# realsense_bridge.net
KiCad netlist of a schematic drawn in Altium Designer
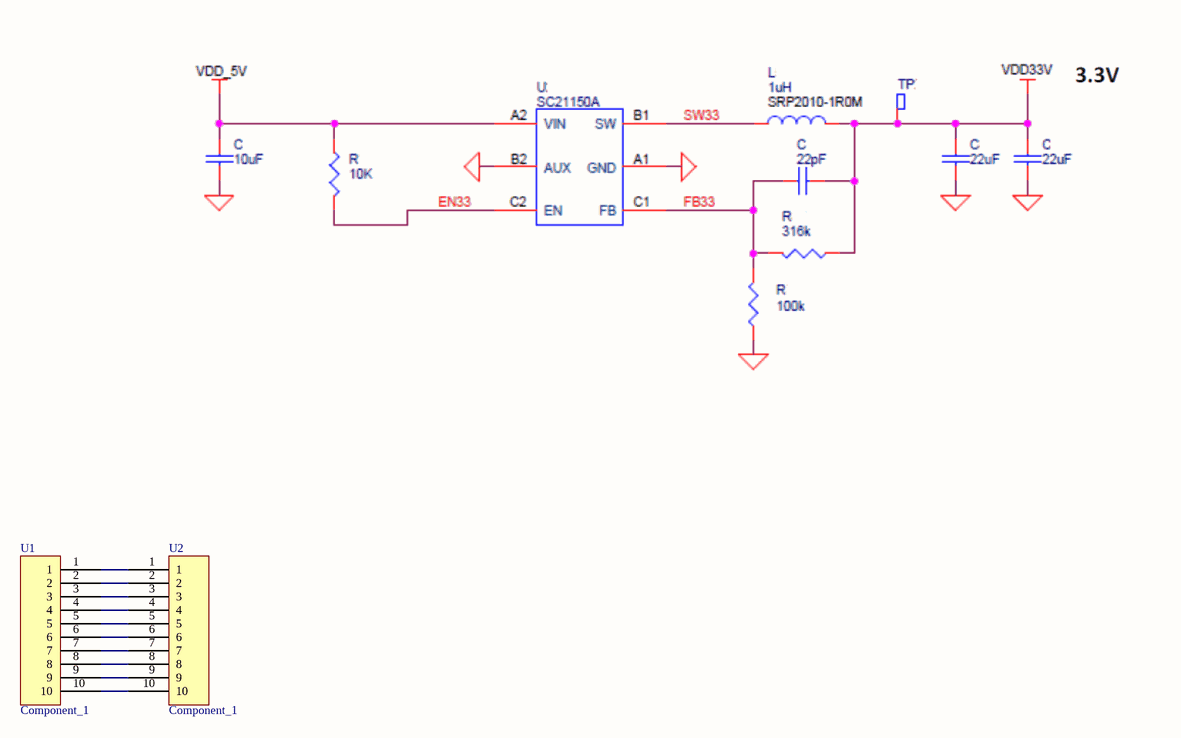
[diagram p0: realsense_bridge.SchDoc]

(export (version "E")
  (design (tool "Eeschema 10.0.6"))
  (components
    (comp (ref "U1")
      (value "Component_1")
      (footprint "IPEX-20346-10T")
      (libsource (lib "") (part "Component_1_1"))
    )
    (comp (ref "U2")
      (value "Component_1")
      (footprint "FPC0.5 2H-WS-10P")
      (libsource (lib "Schlib1") (part "Component_1"))
    )
  )
  (nets
    (net (code "1") (name "Net-(U1-Pad1)") (class "Default")
      (node (ref "U1") (pin "1") (pinfunction "1_1") (pintype "passive"))
      (node (ref "U2") (pin "1") (pinfunction "1_1") (pintype "passive"))
    )
    (net (code "2") (name "Net-(U1-Pad2)") (class "Default")
      (node (ref "U1") (pin "2") (pinfunction "2_2") (pintype "passive"))
      (node (ref "U2") (pin "2") (pinfunction "2_2") (pintype "passive"))
    )
    (net (code "3") (name "Net-(U1-Pad3)") (class "Default")
      (node (ref "U1") (pin "3") (pinfunction "3_3") (pintype "passive"))
      (node (ref "U2") (pin "3") (pinfunction "3_3") (pintype "passive"))
    )
    (net (code "4") (name "Net-(U1-Pad4)") (class "Default")
      (node (ref "U1") (pin "4") (pinfunction "4_4") (pintype "passive"))
      (node (ref "U2") (pin "4") (pinfunction "4_4") (pintype "passive"))
    )
    (net (code "5") (name "Net-(U1-Pad5)") (class "Default")
      (node (ref "U1") (pin "5") (pinfunction "5_5") (pintype "passive"))
      (node (ref "U2") (pin "5") (pinfunction "5_5") (pintype "passive"))
    )
    (net (code "6") (name "Net-(U1-Pad6)") (class "Default")
      (node (ref "U1") (pin "6") (pinfunction "6_6") (pintype "passive"))
      (node (ref "U2") (pin "6") (pinfunction "6_6") (pintype "passive"))
    )
    (net (code "7") (name "Net-(U1-Pad7)") (class "Default")
      (node (ref "U1") (pin "7") (pinfunction "7_7") (pintype "passive"))
      (node (ref "U2") (pin "7") (pinfunction "7_7") (pintype "passive"))
    )
    (net (code "8") (name "Net-(U1-Pad8)") (class "Default")
      (node (ref "U1") (pin "8") (pinfunction "8_8") (pintype "passive"))
      (node (ref "U2") (pin "8") (pinfunction "8_8") (pintype "passive"))
    )
    (net (code "9") (name "Net-(U1-Pad9)") (class "Default")
      (node (ref "U1") (pin "9") (pinfunction "9_9") (pintype "passive"))
      (node (ref "U2") (pin "9") (pinfunction "9_9") (pintype "passive"))
    )
    (net (code "10") (name "Net-(U1-Pad10)") (class "Default")
      (node (ref "U1") (pin "10") (pinfunction "10_10") (pintype "passive"))
      (node (ref "U2") (pin "10") (pinfunction "10_10") (pintype "passive"))
    )
  )
)
